# CH32X035G8R-R0.net
KiCad netlist of a schematic drawn in Altium Designer
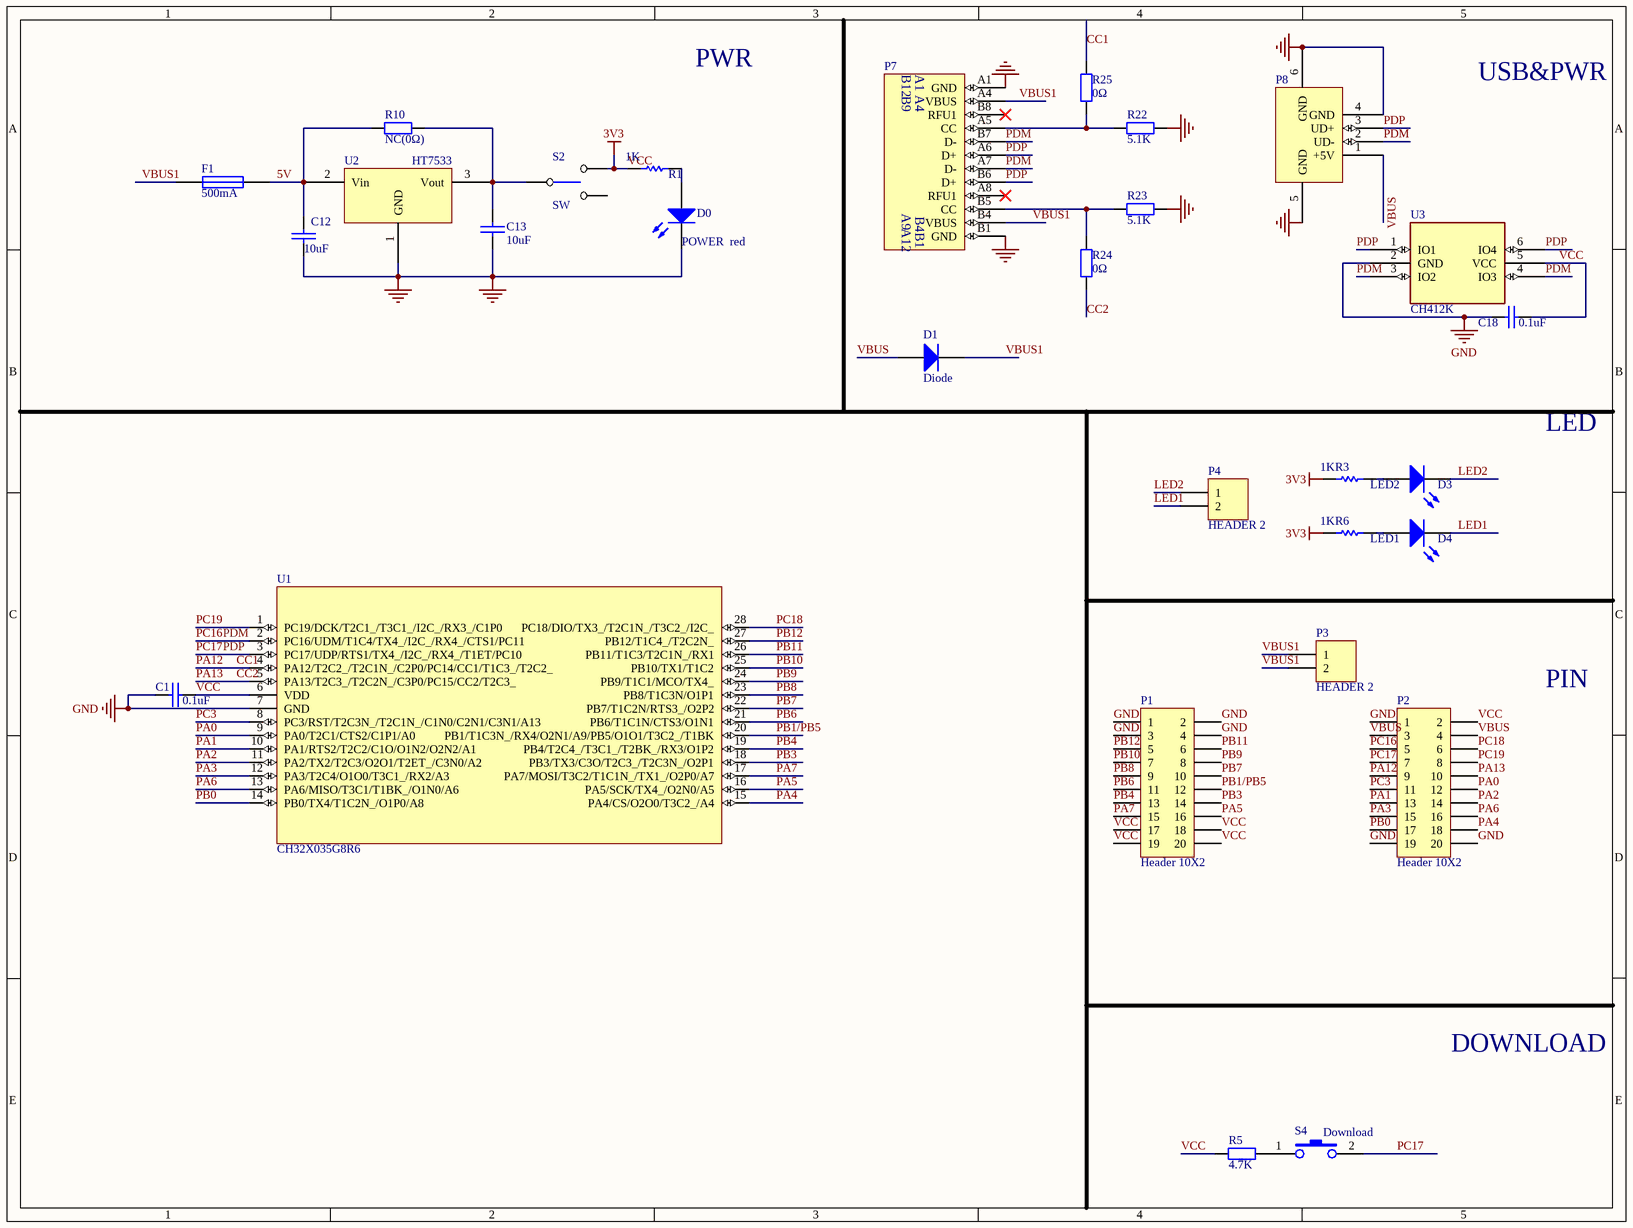
[diagram p0: CH32X035G8R-R0.SchDoc]

(export (version "E")
  (design (tool "Eeschema 10.0.6"))
  (components
    (comp (ref "C1")
      (value "0.1uF")
      (footprint "0603_C")
      (description "Capacitor")
      (libsource (lib "*") (part "CAP"))
    )
    (comp (ref "C12")
      (value "10uF")
      (footprint "0603_C")
      (description "Capacitor")
      (libsource (lib "*") (part "CAP"))
    )
    (comp (ref "C13")
      (value "10uF")
      (footprint "0603_C")
      (description "Capacitor")
      (libsource (lib "*") (part "CAP"))
    )
    (comp (ref "C18")
      (value "0.1uF")
      (footprint "0603_C")
      (description "Capacitor")
      (libsource (lib "Miscellaneous Devices") (part "Cap"))
    )
    (comp (ref "D0")
      (value "POWER  red")
      (footprint "0603+")
      (description "Typical INFRARED GaAs LED")
      (fields (field (name "PUBLISHER") "Altium Limited"))
      (libsource (lib "*") (part "LED0"))
    )
    (comp (ref "D1")
      (value "Diode")
      (footprint "SOD-123")
      (description "Default Diode")
      (fields (field (name "PUBLISHER") "Altium Limited"))
      (libsource (lib "Miscellaneous Devices") (part "Diode"))
    )
    (comp (ref "D3")
      (value "LED2")
      (footprint "0603+")
      (description "Typical INFRARED GaAs LED")
      (fields (field (name "PUBLISHER") "Altium Limited"))
      (libsource (lib "*") (part "LED0"))
    )
    (comp (ref "D4")
      (value "LED1")
      (footprint "0603+")
      (description "Typical INFRARED GaAs LED")
      (fields (field (name "PUBLISHER") "Altium Limited"))
      (libsource (lib "*") (part "LED0"))
    )
    (comp (ref "F1")
      (value "500mA")
      (footprint "0603")
      (description "Fuse")
      (libsource (lib "*") (part "FUSE1"))
    )
    (comp (ref "P1")
      (value "Header 10X2")
      (footprint "IDC20-2.54mm")
      (description "Header, 10-Pin, Dual row")
      (fields (field (name "PUBLISHER") "Altium Limited"))
      (libsource (lib "Miscellaneous Connectors") (part "Header 10X2"))
    )
    (comp (ref "P2")
      (value "Header 10X2")
      (footprint "IDC20-2.54mm")
      (description "Header, 10-Pin, Dual row")
      (fields (field (name "PUBLISHER") "Altium Limited"))
      (libsource (lib "Miscellaneous Connectors") (part "Header 10X2"))
    )
    (comp (ref "P3")
      (value "HEADER 2")
      (footprint "SIP2-2.54mm")
      (description "Header, 2-Pin")
      (libsource (lib "wch_sch_others") (part "HEADER 2"))
    )
    (comp (ref "P4")
      (value "HEADER 2")
      (footprint "SIP2-2.54mm")
      (description "Header, 2-Pin")
      (libsource (lib "wch_sch_others") (part "HEADER 2"))
    )
    (comp (ref "P7")
      (value "TYPE-C")
      (footprint "TYPE-C-Receptacle-2.0")
      (libsource (lib "*") (part "TYPE-C1"))
    )
    (comp (ref "P8")
      (value "USB_A")
      (footprint "USBAF")
      (description "USB Port")
      (libsource (lib "*") (part "USB"))
    )
    (comp (ref "R1")
      (value "1K")
      (footprint "0603")
      (description "Semiconductor Resistor")
      (libsource (lib "*") (part "Res Semi"))
    )
    (comp (ref "R3")
      (value "1K")
      (footprint "0603")
      (description "Semiconductor Resistor")
      (libsource (lib "*") (part "Res Semi"))
    )
    (comp (ref "R5")
      (value "4.7K")
      (footprint "0603")
      (description "Resistor")
      (libsource (lib "Miscellaneous Devices") (part "Res2"))
    )
    (comp (ref "R6")
      (value "1K")
      (footprint "0603")
      (description "Semiconductor Resistor")
      (libsource (lib "*") (part "Res Semi"))
    )
    (comp (ref "R10")
      (value "NC(0Ω)")
      (footprint "0603")
      (description "Resistor")
      (libsource (lib "*") (part "Res2"))
    )
    (comp (ref "R22")
      (value "5.1K")
      (footprint "0603")
      (description "Resistor")
      (libsource (lib "Miscellaneous Devices") (part "Res2"))
    )
    (comp (ref "R23")
      (value "5.1K")
      (footprint "0603")
      (description "Resistor")
      (libsource (lib "Miscellaneous Devices") (part "Res2"))
    )
    (comp (ref "R24")
      (value "0Ω")
      (footprint "0603")
      (description "Resistor")
      (libsource (lib "") (part "Res2_1"))
    )
    (comp (ref "R25")
      (value "0Ω")
      (footprint "0603")
      (description "Resistor")
      (libsource (lib "") (part "Res2_1"))
    )
    (comp (ref "S2") (value "SW") (footprint "SW1") (libsource (lib "*") (part "SW")))
    (comp (ref "S4")
      (value "Download")
      (footprint "SMD_6.1x3.65x2.5mm-KEY")
      (libsource (lib "wch_sch_others") (part "KEY1"))
    )
    (comp (ref "U1")
      (value "CH32X035G8R6")
      (footprint "QSOP28")
      (description "RISC-V MCU with USB/PD/ADC/SPI/I2C/UART/OA/CMP")
      (libsource (lib "CHXXX") (part "CH32X035G8R6"))
    )
    (comp (ref "U2")
      (value "HT7533")
      (footprint "SOT-89")
      (libsource (lib "wch_sch_others") (part "1117-3.3V"))
    )
    (comp (ref "U3")
      (value "CH412K")
      (footprint "SOT-363")
      (description "Qaud ESD protect, high speed")
      (libsource (lib "CHXXX") (part "CH412K"))
    )
  )
  (nets
    (net (code "1") (name "/5V") (class "Default")
      (node (ref "C12") (pin "1") (pinfunction "1_1") (pintype "passive"))
      (node (ref "F1") (pin "2") (pinfunction "2_2") (pintype "passive"))
      (node (ref "R10") (pin "2") (pinfunction "2_2") (pintype "passive"))
      (node (ref "U2") (pin "2") (pinfunction "Vin_2") (pintype "passive"))
    )
    (net (code "3") (name "/CC1") (class "Default")
      (node (ref "P2") (pin "9") (pinfunction "9_9") (pintype "passive"))
      (node (ref "R25") (pin "2") (pinfunction "2_2") (pintype "passive"))
      (node (ref "U1") (pin "4") (pinfunction "PA12/T2C2_/T2C1N_/C2P0/PC14/CC1/T1C3_/T2C2__4") (pintype "bidirectional"))
    )
    (net (code "4") (name "/CC2") (class "Default")
      (node (ref "P2") (pin "10") (pinfunction "10_10") (pintype "passive"))
      (node (ref "R24") (pin "1") (pinfunction "1_1") (pintype "passive"))
      (node (ref "U1") (pin "5") (pinfunction "PA13/T2C3_/T2C2N_/C3P0/PC15/CC2/T2C3__5") (pintype "bidirectional"))
    )
    (net (code "5") (name "/LED1") (class "Default")
      (node (ref "D4") (pin "2") (pinfunction "K_2") (pintype "passive"))
      (node (ref "P4") (pin "2") (pinfunction "2_2") (pintype "passive"))
    )
    (net (code "6") (name "/LED2") (class "Default")
      (node (ref "D3") (pin "2") (pinfunction "K_2") (pintype "passive"))
      (node (ref "P4") (pin "1") (pinfunction "1_1") (pintype "passive"))
    )
    (net (code "7") (name "/PA0") (class "Default")
      (node (ref "P2") (pin "12") (pinfunction "12_12") (pintype "passive"))
      (node (ref "U1") (pin "9") (pinfunction "PA0/T2C1/CTS2/C1P1/A0_9") (pintype "bidirectional"))
    )
    (net (code "8") (name "/PA1") (class "Default")
      (node (ref "P2") (pin "13") (pinfunction "13_13") (pintype "passive"))
      (node (ref "U1") (pin "10") (pinfunction "PA1/RTS2/T2C2/C1O/O1N2/O2N2/A1_10") (pintype "bidirectional"))
    )
    (net (code "9") (name "/PA2") (class "Default")
      (node (ref "P2") (pin "14") (pinfunction "14_14") (pintype "passive"))
      (node (ref "U1") (pin "11") (pinfunction "PA2/TX2/T2C3/O2O1/T2ET_/C3N0/A2_11") (pintype "bidirectional"))
    )
    (net (code "10") (name "/PA3") (class "Default")
      (node (ref "P2") (pin "15") (pinfunction "15_15") (pintype "passive"))
      (node (ref "U1") (pin "12") (pinfunction "PA3/T2C4/O1O0/T3C1_/RX2/A3_12") (pintype "bidirectional"))
    )
    (net (code "11") (name "/PA4") (class "Default")
      (node (ref "P2") (pin "18") (pinfunction "18_18") (pintype "passive"))
      (node (ref "U1") (pin "15") (pinfunction "PA4/CS/O2O0/T3C2_/A4_15") (pintype "bidirectional"))
    )
    (net (code "12") (name "/PA5") (class "Default")
      (node (ref "P1") (pin "16") (pinfunction "16_16") (pintype "passive"))
      (node (ref "U1") (pin "16") (pinfunction "PA5/SCK/TX4_/O2N0/A5_16") (pintype "bidirectional"))
    )
    (net (code "13") (name "/PA6") (class "Default")
      (node (ref "P2") (pin "16") (pinfunction "16_16") (pintype "passive"))
      (node (ref "U1") (pin "13") (pinfunction "PA6/MISO/T3C1/T1BK_/O1N0/A6_13") (pintype "bidirectional"))
    )
    (net (code "14") (name "/PA7") (class "Default")
      (node (ref "P1") (pin "15") (pinfunction "15_15") (pintype "passive"))
      (node (ref "U1") (pin "17") (pinfunction "PA7/MOSI/T3C2/T1C1N_/TX1_/O2P0/A7_17") (pintype "bidirectional"))
    )
    (net (code "15") (name "/PB0") (class "Default")
      (node (ref "P2") (pin "17") (pinfunction "17_17") (pintype "passive"))
      (node (ref "U1") (pin "14") (pinfunction "PB0/TX4/T1C2N_/O1P0/A8_14") (pintype "bidirectional"))
    )
    (net (code "16") (name "/PB1{slash}PB5") (class "Default")
      (node (ref "P1") (pin "12") (pinfunction "12_12") (pintype "passive"))
      (node (ref "U1") (pin "20") (pinfunction "PB1/T1C3N_/RX4/O2N1/A9/PB5/O1O1/T3C2_/T1BK_20") (pintype "bidirectional"))
    )
    (net (code "17") (name "/PB3") (class "Default")
      (node (ref "P1") (pin "14") (pinfunction "14_14") (pintype "passive"))
      (node (ref "U1") (pin "18") (pinfunction "PB3/TX3/C3O/T2C3_/T2C3N_/O2P1_18") (pintype "bidirectional"))
    )
    (net (code "18") (name "/PB4") (class "Default")
      (node (ref "P1") (pin "13") (pinfunction "13_13") (pintype "passive"))
      (node (ref "U1") (pin "19") (pinfunction "PB4/T2C4_/T3C1_/T2BK_/RX3/O1P2_19") (pintype "bidirectional"))
    )
    (net (code "19") (name "/PB6") (class "Default")
      (node (ref "P1") (pin "11") (pinfunction "11_11") (pintype "passive"))
      (node (ref "U1") (pin "21") (pinfunction "PB6/T1C1N/CTS3/O1N1_21") (pintype "bidirectional"))
    )
    (net (code "20") (name "/PB7") (class "Default")
      (node (ref "P1") (pin "10") (pinfunction "10_10") (pintype "passive"))
      (node (ref "U1") (pin "22") (pinfunction "PB7/T1C2N/RTS3_/O2P2_22") (pintype "bidirectional"))
    )
    (net (code "21") (name "/PB8") (class "Default")
      (node (ref "P1") (pin "9") (pinfunction "9_9") (pintype "passive"))
      (node (ref "U1") (pin "23") (pinfunction "PB8/T1C3N/O1P1_23") (pintype "bidirectional"))
    )
    (net (code "22") (name "/PB9") (class "Default")
      (node (ref "P1") (pin "8") (pinfunction "8_8") (pintype "passive"))
      (node (ref "U1") (pin "24") (pinfunction "PB9/T1C1/MCO/TX4__24") (pintype "bidirectional"))
    )
    (net (code "23") (name "/PB10") (class "Default")
      (node (ref "P1") (pin "7") (pinfunction "7_7") (pintype "passive"))
      (node (ref "U1") (pin "25") (pinfunction "PB10/TX1/T1C2_25") (pintype "bidirectional"))
    )
    (net (code "24") (name "/PB11") (class "Default")
      (node (ref "P1") (pin "6") (pinfunction "6_6") (pintype "passive"))
      (node (ref "U1") (pin "26") (pinfunction "PB11/T1C3/T2C1N_/RX1_26") (pintype "bidirectional"))
    )
    (net (code "25") (name "/PB12") (class "Default")
      (node (ref "P1") (pin "5") (pinfunction "5_5") (pintype "passive"))
      (node (ref "U1") (pin "27") (pinfunction "PB12/T1C4_/T2C2N__27") (pintype "bidirectional"))
    )
    (net (code "26") (name "/PC3") (class "Default")
      (node (ref "P2") (pin "11") (pinfunction "11_11") (pintype "passive"))
      (node (ref "U1") (pin "8") (pinfunction "PC3/RST/T2C3N_/T2C1N_/C1N0/C2N1/C3N1/A13_8") (pintype "bidirectional"))
    )
    (net (code "27") (name "/PC16") (class "Default")
      (node (ref "P2") (pin "5") (pinfunction "5_5") (pintype "passive"))
      (node (ref "P7") (pin "A7") (pinfunction "D-_A7") (pintype "bidirectional"))
      (node (ref "P7") (pin "B7") (pinfunction "D-_B7") (pintype "bidirectional"))
      (node (ref "P8") (pin "2") (pinfunction "UD-_2") (pintype "bidirectional"))
      (node (ref "U1") (pin "2") (pinfunction "PC16/UDM/T1C4/TX4_/I2C_/RX4_/CTS1/PC11_2") (pintype "bidirectional"))
      (node (ref "U3") (pin "3") (pinfunction "IO2_3") (pintype "bidirectional"))
      (node (ref "U3") (pin "4") (pinfunction "IO3_4") (pintype "bidirectional"))
    )
    (net (code "28") (name "/PC17") (class "Default")
      (node (ref "P2") (pin "7") (pinfunction "7_7") (pintype "passive"))
      (node (ref "P7") (pin "A6") (pinfunction "D+_A6") (pintype "bidirectional"))
      (node (ref "P7") (pin "B6") (pinfunction "D+_B6") (pintype "bidirectional"))
      (node (ref "P8") (pin "3") (pinfunction "UD+_3") (pintype "bidirectional"))
      (node (ref "S4") (pin "2") (pinfunction "2_2") (pintype "passive"))
      (node (ref "U1") (pin "3") (pinfunction "PC17/UDP/RTS1/TX4_/I2C_/RX4_/T1ET/PC10_3") (pintype "bidirectional"))
      (node (ref "U3") (pin "1") (pinfunction "IO1_1") (pintype "bidirectional"))
      (node (ref "U3") (pin "6") (pinfunction "IO4_6") (pintype "bidirectional"))
    )
    (net (code "29") (name "/PC18") (class "Default")
      (node (ref "P2") (pin "6") (pinfunction "6_6") (pintype "passive"))
      (node (ref "U1") (pin "28") (pinfunction "PC18/DIO/TX3_/T2C1N_/T3C2_/I2C__28") (pintype "bidirectional"))
    )
    (net (code "30") (name "/PC19") (class "Default")
      (node (ref "P2") (pin "8") (pinfunction "8_8") (pintype "passive"))
      (node (ref "U1") (pin "1") (pinfunction "PC19/DCK/T2C1_/T3C1_/I2C_/RX3_/C1P0_1") (pintype "bidirectional"))
    )
    (net (code "31") (name "/VBUS") (class "Default")
      (node (ref "D1") (pin "1") (pinfunction "A_1") (pintype "passive"))
      (node (ref "P2") (pin "3") (pinfunction "3_3") (pintype "passive"))
      (node (ref "P2") (pin "4") (pinfunction "4_4") (pintype "passive"))
      (node (ref "P8") (pin "1") (pinfunction "+5V_1") (pintype "power_in"))
    )
    (net (code "32") (name "/VBUS1") (class "Default")
      (node (ref "D1") (pin "2") (pinfunction "K_2") (pintype "passive"))
      (node (ref "F1") (pin "1") (pinfunction "1_1") (pintype "passive"))
      (node (ref "P3") (pin "1") (pinfunction "1_1") (pintype "passive"))
      (node (ref "P3") (pin "2") (pinfunction "2_2") (pintype "passive"))
      (node (ref "P7") (pin "A4") (pinfunction "VBUS_A4") (pintype "bidirectional"))
      (node (ref "P7") (pin "B4") (pinfunction "VBUS_B4") (pintype "bidirectional"))
    )
    (net (code "33") (name "3V3") (class "Default")
      (node (ref "C1") (pin "2") (pinfunction "2_2") (pintype "passive"))
      (node (ref "C18") (pin "2") (pinfunction "2_2") (pintype "passive"))
      (node (ref "P1") (pin "17") (pinfunction "17_17") (pintype "passive"))
      (node (ref "P1") (pin "18") (pinfunction "18_18") (pintype "passive"))
      (node (ref "P1") (pin "19") (pinfunction "19_19") (pintype "passive"))
      (node (ref "P1") (pin "20") (pinfunction "20_20") (pintype "passive"))
      (node (ref "P2") (pin "2") (pinfunction "2_2") (pintype "passive"))
      (node (ref "R1") (pin "2") (pinfunction "2_2") (pintype "passive"))
      (node (ref "R3") (pin "1") (pinfunction "1_1") (pintype "passive"))
      (node (ref "R5") (pin "1") (pinfunction "1_1") (pintype "passive"))
      (node (ref "R6") (pin "1") (pinfunction "1_1") (pintype "passive"))
      (node (ref "S2") (pin "3") (pinfunction "3_3") (pintype "passive"))
      (node (ref "U1") (pin "6") (pinfunction "VDD_6") (pintype "power_in"))
      (node (ref "U3") (pin "5") (pinfunction "VCC_5") (pintype "power_in"))
    )
    (net (code "34") (name "GND") (class "Default")
      (node (ref "C1") (pin "1") (pinfunction "1_1") (pintype "passive"))
      (node (ref "C12") (pin "2") (pinfunction "2_2") (pintype "passive"))
      (node (ref "C13") (pin "2") (pinfunction "2_2") (pintype "passive"))
      (node (ref "C18") (pin "1") (pinfunction "1_1") (pintype "passive"))
      (node (ref "D0") (pin "2") (pinfunction "K_2") (pintype "passive"))
      (node (ref "P1") (pin "1") (pinfunction "1_1") (pintype "passive"))
      (node (ref "P1") (pin "2") (pinfunction "2_2") (pintype "passive"))
      (node (ref "P1") (pin "3") (pinfunction "3_3") (pintype "passive"))
      (node (ref "P1") (pin "4") (pinfunction "4_4") (pintype "passive"))
      (node (ref "P2") (pin "1") (pinfunction "1_1") (pintype "passive"))
      (node (ref "P2") (pin "19") (pinfunction "19_19") (pintype "passive"))
      (node (ref "P2") (pin "20") (pinfunction "20_20") (pintype "passive"))
      (node (ref "P7") (pin "A1") (pinfunction "GND_A1") (pintype "bidirectional"))
      (node (ref "P7") (pin "B1") (pinfunction "GND_B1") (pintype "bidirectional"))
      (node (ref "P8") (pin "4") (pinfunction "GND_4") (pintype "power_in"))
      (node (ref "P8") (pin "5") (pinfunction "GND_5") (pintype "power_in"))
      (node (ref "P8") (pin "6") (pinfunction "GND_6") (pintype "power_in"))
      (node (ref "R22") (pin "2") (pinfunction "2_2") (pintype "passive"))
      (node (ref "R23") (pin "2") (pinfunction "2_2") (pintype "passive"))
      (node (ref "U1") (pin "7") (pinfunction "GND_7") (pintype "power_in"))
      (node (ref "U2") (pin "1") (pinfunction "GND_1") (pintype "passive"))
      (node (ref "U3") (pin "2") (pinfunction "GND_2") (pintype "power_in"))
    )
    (net (code "35") (name "Net-(D0-A)") (class "Default")
      (node (ref "D0") (pin "1") (pinfunction "A_1") (pintype "passive"))
      (node (ref "R1") (pin "1") (pinfunction "1_1") (pintype "passive"))
    )
    (net (code "36") (name "Net-(D3-A)") (class "Default")
      (node (ref "D3") (pin "1") (pinfunction "A_1") (pintype "passive"))
      (node (ref "R3") (pin "2") (pinfunction "2_2") (pintype "passive"))
    )
    (net (code "37") (name "Net-(D4-A)") (class "Default")
      (node (ref "D4") (pin "1") (pinfunction "A_1") (pintype "passive"))
      (node (ref "R6") (pin "2") (pinfunction "2_2") (pintype "passive"))
    )
    (net (code "38") (name "Net-(P7-CC-PadA5)") (class "Default")
      (node (ref "P7") (pin "A5") (pinfunction "CC_A5") (pintype "bidirectional"))
      (node (ref "R22") (pin "1") (pinfunction "1_1") (pintype "passive"))
      (node (ref "R25") (pin "1") (pinfunction "1_1") (pintype "passive"))
    )
    (net (code "39") (name "Net-(P7-CC-PadB5)") (class "Default")
      (node (ref "P7") (pin "B5") (pinfunction "CC_B5") (pintype "bidirectional"))
      (node (ref "R23") (pin "1") (pinfunction "1_1") (pintype "passive"))
      (node (ref "R24") (pin "2") (pinfunction "2_2") (pintype "passive"))
    )
    (net (code "40") (name "Net-(R5-Pad2)") (class "Default")
      (node (ref "R5") (pin "2") (pinfunction "2_2") (pintype "passive"))
      (node (ref "S4") (pin "1") (pinfunction "1_1") (pintype "passive"))
    )
    (net (code "41") (name "Net-(U2-Vout)") (class "Default")
      (node (ref "C13") (pin "1") (pinfunction "1_1") (pintype "passive"))
      (node (ref "R10") (pin "1") (pinfunction "1_1") (pintype "passive"))
      (node (ref "S2") (pin "1") (pinfunction "1_1") (pintype "passive"))
      (node (ref "U2") (pin "3") (pinfunction "Vout_3") (pintype "passive"))
    )
    (net (code "42") (name "unconnected-(P7-RFU1-PadA8)") (class "Default")
      (node (ref "P7") (pin "A8") (pinfunction "RFU1_A8") (pintype "bidirectional+no_connect"))
    )
    (net (code "43") (name "unconnected-(P7-RFU1-PadB8)") (class "Default")
      (node (ref "P7") (pin "B8") (pinfunction "RFU1_B8") (pintype "bidirectional+no_connect"))
    )
    (net (code "44") (name "unconnected-(S2-Pad2)") (class "Default")
      (node (ref "S2") (pin "2") (pinfunction "2_2") (pintype "passive"))
    )
  )
)
